# untitled.net
KiCad netlist of a schematic drawn in EAGLE
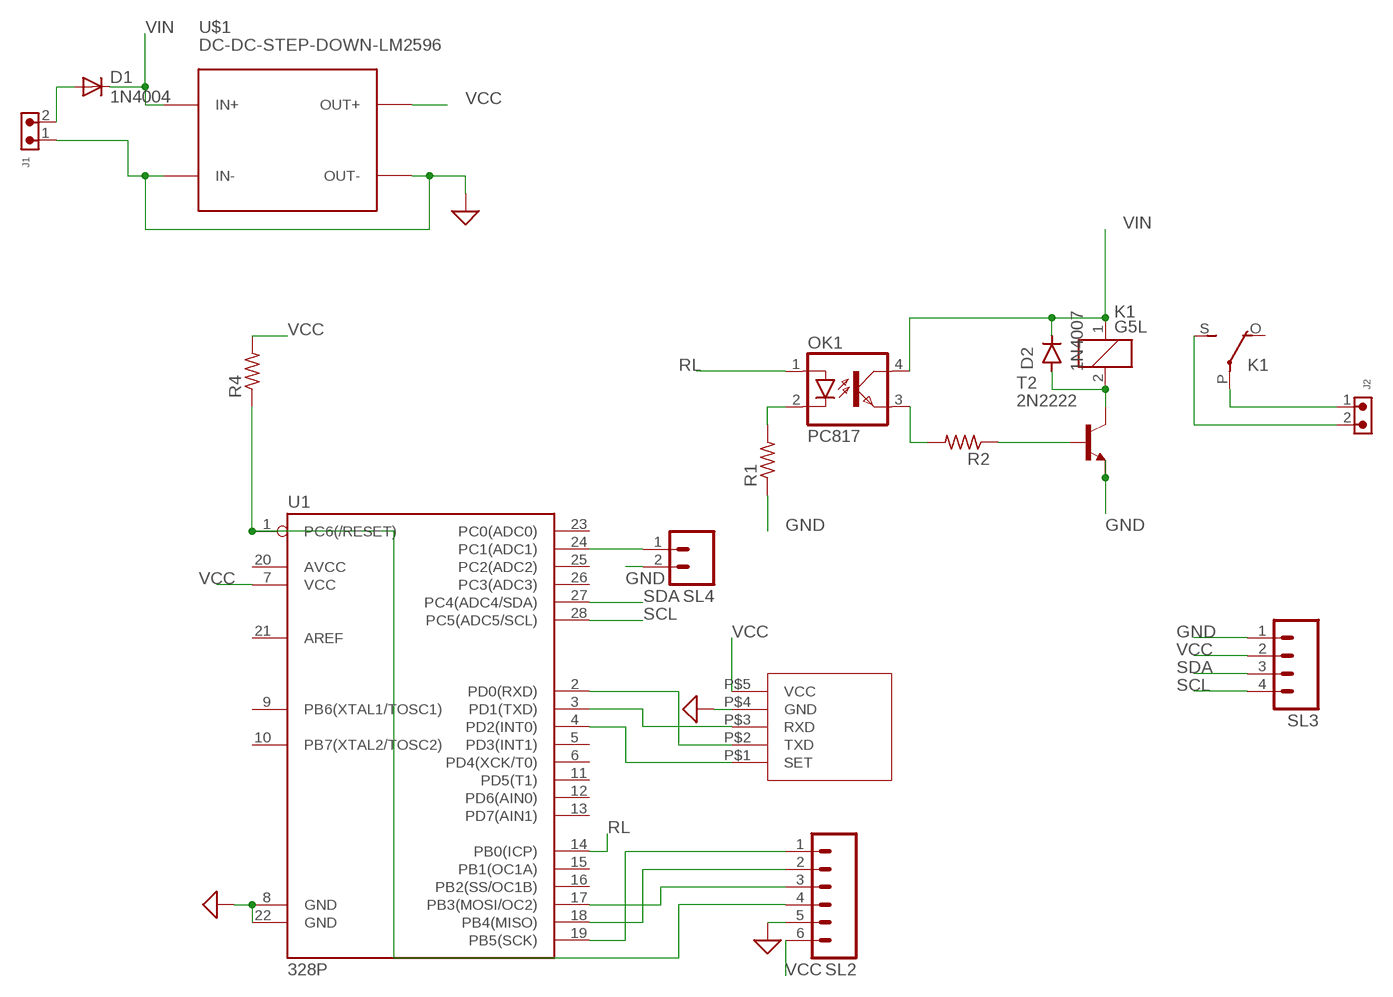
[diagram p0: schematic, sheet 1]

(export (version "E")
  (design (tool "Eeschema 10.0.6"))
  (components
    (comp (ref "D1")
      (value "1N4004")
      (footprint "eagle-import:DO41-10")
      (libsource (lib "eagle-import") (part "1N4004"))
    )
    (comp (ref "D2")
      (value "1N4007")
      (footprint "eagle-import:DO-41")
      (fields
        (field (name "DIGIKEY_PART_NUMBER") "1N4007MSCT-ND")
        (field (name "MANUFACTURER") "Micro Commercial Co")
        (field (name "CREATED_BY") "PCBLayout.com")
      )
      (libsource (lib "eagle-import") (part "1N4007"))
    )
    (comp (ref "J1")
      (value "691305530002")
      (footprint "eagle-import:691305530002")
      (libsource (lib "eagle-import") (part "691305530002"))
    )
    (comp (ref "J2")
      (value "691305530002")
      (footprint "eagle-import:691305530002")
      (libsource (lib "eagle-import") (part "691305530002"))
    )
    (comp (ref "K1")
      (value "G5L")
      (footprint "eagle-import:G5LE")
      (libsource (lib "eagle-import") (part "G5L"))
    )
    (comp (ref "OK1")
      (value "PC817")
      (footprint "eagle-import:DIL04")
      (fields (field (name "MPN") "PC817X4J000F"))
      (libsource (lib "eagle-import") (part "PC817"))
    )
    (comp (ref "R1")
      (value "R-US_0207/7")
      (footprint "eagle-import:0207_7")
      (libsource (lib "eagle-import") (part "R-US_0207/7"))
    )
    (comp (ref "R2")
      (value "R-US_0207/12")
      (footprint "eagle-import:0207_12")
      (libsource (lib "eagle-import") (part "R-US_0207/12"))
    )
    (comp (ref "R4")
      (value "R-US_0207/7")
      (footprint "eagle-import:0207_7")
      (libsource (lib "eagle-import") (part "R-US_0207/7"))
    )
    (comp (ref "SL2")
      (value "M06")
      (footprint "eagle-import:06P")
      (libsource (lib "eagle-import") (part "M06"))
    )
    (comp (ref "SL3")
      (value "M04")
      (footprint "eagle-import:04P")
      (libsource (lib "eagle-import") (part "M04"))
    )
    (comp (ref "SL4")
      (value "M02")
      (footprint "eagle-import:02P")
      (libsource (lib "eagle-import") (part "M02"))
    )
    (comp (ref "T2")
      (value "2N2222")
      (footprint "eagle-import:TO92-EBC-OVAL")
      (libsource (lib "eagle-import") (part "2N2222"))
    )
    (comp (ref "U$1")
      (value "DC-DC-STEP-DOWN-LM2596")
      (footprint "eagle-import:DC-DC-STEP-DOWN-LM2596")
      (libsource (lib "eagle-import") (part "DC-DC-STEP-DOWN-LM2596"))
    )
    (comp (ref "U$3")
      (value "HC12")
      (footprint "eagle-import:HC12")
      (libsource (lib "eagle-import") (part "HC12"))
    )
    (comp (ref "U1")
      (value "328P")
      (footprint "eagle-import:DIP28")
      (libsource (lib "eagle-import") (part "ATMEGA328P_PDIP"))
    )
  )
  (nets
    (net (code "1") (name "/RL") (class "Default")
      (node (ref "OK1") (pin "1") (pinfunction "A_1") (pintype "passive"))
      (node (ref "U1") (pin "14") (pinfunction "PB0(ICP)_14") (pintype "bidirectional"))
    )
    (net (code "2") (name "/SCL") (class "Default")
      (node (ref "SL3") (pin "4") (pinfunction "4_4") (pintype "passive"))
      (node (ref "U1") (pin "28") (pinfunction "PC5(ADC5/SCL)_28") (pintype "bidirectional"))
    )
    (net (code "3") (name "/SDA") (class "Default")
      (node (ref "SL3") (pin "3") (pinfunction "3_3") (pintype "passive"))
      (node (ref "U1") (pin "27") (pinfunction "PC4(ADC4/SDA)_27") (pintype "bidirectional"))
    )
    (net (code "4") (name "/VCC") (class "Default")
      (node (ref "R4") (pin "2") (pinfunction "2_2") (pintype "passive"))
      (node (ref "SL2") (pin "6") (pinfunction "6_6") (pintype "passive"))
      (node (ref "SL3") (pin "2") (pinfunction "2_2") (pintype "passive"))
      (node (ref "U$1") (pin "OUT+") (pinfunction "OUT+_OUT+") (pintype "bidirectional"))
      (node (ref "U$3") (pin "P$5") (pinfunction "VCC_P$5") (pintype "bidirectional"))
      (node (ref "U1") (pin "7") (pinfunction "VCC_7") (pintype "bidirectional"))
    )
    (net (code "5") (name "/VIN") (class "Default")
      (node (ref "D1") (pin "C") (pinfunction "C_C") (pintype "passive"))
      (node (ref "D2") (pin "C") (pinfunction "C_C") (pintype "passive"))
      (node (ref "K1") (pin "1") (pinfunction "1_1") (pintype "passive"))
      (node (ref "OK1") (pin "4") (pinfunction "COL_4") (pintype "passive"))
      (node (ref "U$1") (pin "IN+") (pinfunction "IN+_IN+") (pintype "bidirectional"))
    )
    (net (code "6") (name "Net-(D1-PadA)") (class "Default")
      (node (ref "D1") (pin "A") (pinfunction "A_A") (pintype "passive"))
      (node (ref "J1") (pin "2") (pinfunction "2_2") (pintype "passive"))
    )
    (net (code "7") (name "Net-(D2-PadA)") (class "Default")
      (node (ref "D2") (pin "A") (pinfunction "A_A") (pintype "passive"))
      (node (ref "K1") (pin "2") (pinfunction "2_2") (pintype "passive"))
      (node (ref "T2") (pin "C") (pinfunction "C_C") (pintype "passive"))
    )
    (net (code "8") (name "Net-(J2-Pad1)") (class "Default")
      (node (ref "J2") (pin "1") (pinfunction "1_1") (pintype "passive"))
      (node (ref "K1") (pin "P") (pinfunction "P_P") (pintype "passive"))
    )
    (net (code "9") (name "Net-(J2-Pad2)") (class "Default")
      (node (ref "J2") (pin "2") (pinfunction "2_2") (pintype "passive"))
      (node (ref "K1") (pin "S") (pinfunction "S_S") (pintype "passive"))
    )
    (net (code "10") (name "Net-(OK1-C)") (class "Default")
      (node (ref "OK1") (pin "2") (pinfunction "C_2") (pintype "passive"))
      (node (ref "R1") (pin "2") (pinfunction "2_2") (pintype "passive"))
    )
    (net (code "11") (name "Net-(OK1-EMIT)") (class "Default")
      (node (ref "OK1") (pin "3") (pinfunction "EMIT_3") (pintype "passive"))
      (node (ref "R2") (pin "2") (pinfunction "2_2") (pintype "passive"))
    )
    (net (code "12") (name "Net-(R2-Pad1)") (class "Default")
      (node (ref "R2") (pin "1") (pinfunction "1_1") (pintype "passive"))
      (node (ref "T2") (pin "B") (pinfunction "B_B") (pintype "passive"))
    )
    (net (code "13") (name "Net-(U$3-RXD)") (class "Default")
      (node (ref "U$3") (pin "P$3") (pinfunction "RXD_P$3") (pintype "bidirectional"))
      (node (ref "U1") (pin "3") (pinfunction "PD1(TXD)_3") (pintype "bidirectional"))
    )
    (net (code "14") (name "Net-(U$3-SET)") (class "Default")
      (node (ref "U$3") (pin "P$1") (pinfunction "SET_P$1") (pintype "bidirectional"))
      (node (ref "U1") (pin "4") (pinfunction "PD2(INT0)_4") (pintype "bidirectional"))
    )
    (net (code "15") (name "Net-(U$3-TXD)") (class "Default")
      (node (ref "U$3") (pin "P$2") (pinfunction "TXD_P$2") (pintype "bidirectional"))
      (node (ref "U1") (pin "2") (pinfunction "PD0(RXD)_2") (pintype "bidirectional"))
    )
    (net (code "16") (name "Net-(U1-PB3(MOSI{slash}OC2))") (class "Default")
      (node (ref "SL2") (pin "3") (pinfunction "3_3") (pintype "passive"))
      (node (ref "U1") (pin "17") (pinfunction "PB3(MOSI/OC2)_17") (pintype "bidirectional"))
    )
    (net (code "17") (name "Net-(U1-PB4(MISO))") (class "Default")
      (node (ref "SL2") (pin "2") (pinfunction "2_2") (pintype "passive"))
      (node (ref "U1") (pin "18") (pinfunction "PB4(MISO)_18") (pintype "bidirectional"))
    )
    (net (code "18") (name "Net-(U1-PB5(SCK))") (class "Default")
      (node (ref "SL2") (pin "1") (pinfunction "1_1") (pintype "passive"))
      (node (ref "U1") (pin "19") (pinfunction "PB5(SCK)_19") (pintype "bidirectional"))
    )
    (net (code "19") (name "Net-(U1-PC1(ADC1))") (class "Default")
      (node (ref "SL4") (pin "1") (pinfunction "1_1") (pintype "passive"))
      (node (ref "U1") (pin "24") (pinfunction "PC1(ADC1)_24") (pintype "bidirectional"))
    )
    (net (code "20") (name "Net-(U1-PC6({slash}RESET))") (class "Default")
      (node (ref "R4") (pin "1") (pinfunction "1_1") (pintype "passive"))
      (node (ref "SL2") (pin "4") (pinfunction "4_4") (pintype "passive"))
      (node (ref "U1") (pin "1") (pinfunction "PC6(/RESET)_1") (pintype "bidirectional"))
    )
    (net (code "21") (name "SUP") (class "Default")
      (node (ref "J1") (pin "1") (pinfunction "1_1") (pintype "passive"))
      (node (ref "R1") (pin "1") (pinfunction "1_1") (pintype "passive"))
      (node (ref "SL2") (pin "5") (pinfunction "5_5") (pintype "passive"))
      (node (ref "SL3") (pin "1") (pinfunction "1_1") (pintype "passive"))
      (node (ref "SL4") (pin "2") (pinfunction "2_2") (pintype "passive"))
      (node (ref "T2") (pin "E") (pinfunction "E_E") (pintype "passive"))
      (node (ref "U$1") (pin "IN-") (pinfunction "IN-_IN-") (pintype "bidirectional"))
      (node (ref "U$1") (pin "OUT-") (pinfunction "OUT-_OUT-") (pintype "bidirectional"))
      (node (ref "U$3") (pin "P$4") (pinfunction "GND_P$4") (pintype "bidirectional"))
      (node (ref "U1") (pin "22") (pinfunction "GND_22") (pintype "bidirectional"))
      (node (ref "U1") (pin "8") (pinfunction "GND_8") (pintype "bidirectional"))
    )
    (net (code "22") (name "unconnected-(K1-PadO)") (class "Default")
      (node (ref "K1") (pin "O") (pinfunction "O_O") (pintype "passive"))
    )
    (net (code "23") (name "unconnected-(U1-AREF-Pad21)") (class "Default")
      (node (ref "U1") (pin "21") (pinfunction "AREF_21") (pintype "bidirectional"))
    )
    (net (code "24") (name "unconnected-(U1-AVCC-Pad20)") (class "Default")
      (node (ref "U1") (pin "20") (pinfunction "AVCC_20") (pintype "bidirectional"))
    )
    (net (code "25") (name "unconnected-(U1-PB1(OC1A)-Pad15)") (class "Default")
      (node (ref "U1") (pin "15") (pinfunction "PB1(OC1A)_15") (pintype "bidirectional"))
    )
    (net (code "26") (name "unconnected-(U1-PB2(SS{slash}OC1B)-Pad16)") (class "Default")
      (node (ref "U1") (pin "16") (pinfunction "PB2(SS/OC1B)_16") (pintype "bidirectional"))
    )
    (net (code "27") (name "unconnected-(U1-PB6(XTAL1{slash}TOSC1)-Pad9)") (class "Default")
      (node (ref "U1") (pin "9") (pinfunction "PB6(XTAL1/TOSC1)_9") (pintype "bidirectional"))
    )
    (net (code "28") (name "unconnected-(U1-PB7(XTAL2{slash}TOSC2)-Pad10)") (class "Default")
      (node (ref "U1") (pin "10") (pinfunction "PB7(XTAL2/TOSC2)_10") (pintype "bidirectional"))
    )
    (net (code "29") (name "unconnected-(U1-PC0(ADC0)-Pad23)") (class "Default")
      (node (ref "U1") (pin "23") (pinfunction "PC0(ADC0)_23") (pintype "bidirectional"))
    )
    (net (code "30") (name "unconnected-(U1-PC2(ADC2)-Pad25)") (class "Default")
      (node (ref "U1") (pin "25") (pinfunction "PC2(ADC2)_25") (pintype "bidirectional"))
    )
    (net (code "31") (name "unconnected-(U1-PC3(ADC3)-Pad26)") (class "Default")
      (node (ref "U1") (pin "26") (pinfunction "PC3(ADC3)_26") (pintype "bidirectional"))
    )
    (net (code "32") (name "unconnected-(U1-PD3(INT1)-Pad5)") (class "Default")
      (node (ref "U1") (pin "5") (pinfunction "PD3(INT1)_5") (pintype "bidirectional"))
    )
    (net (code "33") (name "unconnected-(U1-PD4(XCK{slash}T0)-Pad6)") (class "Default")
      (node (ref "U1") (pin "6") (pinfunction "PD4(XCK/T0)_6") (pintype "bidirectional"))
    )
    (net (code "34") (name "unconnected-(U1-PD5(T1)-Pad11)") (class "Default")
      (node (ref "U1") (pin "11") (pinfunction "PD5(T1)_11") (pintype "bidirectional"))
    )
    (net (code "35") (name "unconnected-(U1-PD6(AIN0)-Pad12)") (class "Default")
      (node (ref "U1") (pin "12") (pinfunction "PD6(AIN0)_12") (pintype "bidirectional"))
    )
    (net (code "36") (name "unconnected-(U1-PD7(AIN1)-Pad13)") (class "Default")
      (node (ref "U1") (pin "13") (pinfunction "PD7(AIN1)_13") (pintype "bidirectional"))
    )
  )
)
